# 04C-004_Adjustable_Analog_Front_End.net
KiCad netlist of a schematic drawn in EAGLE
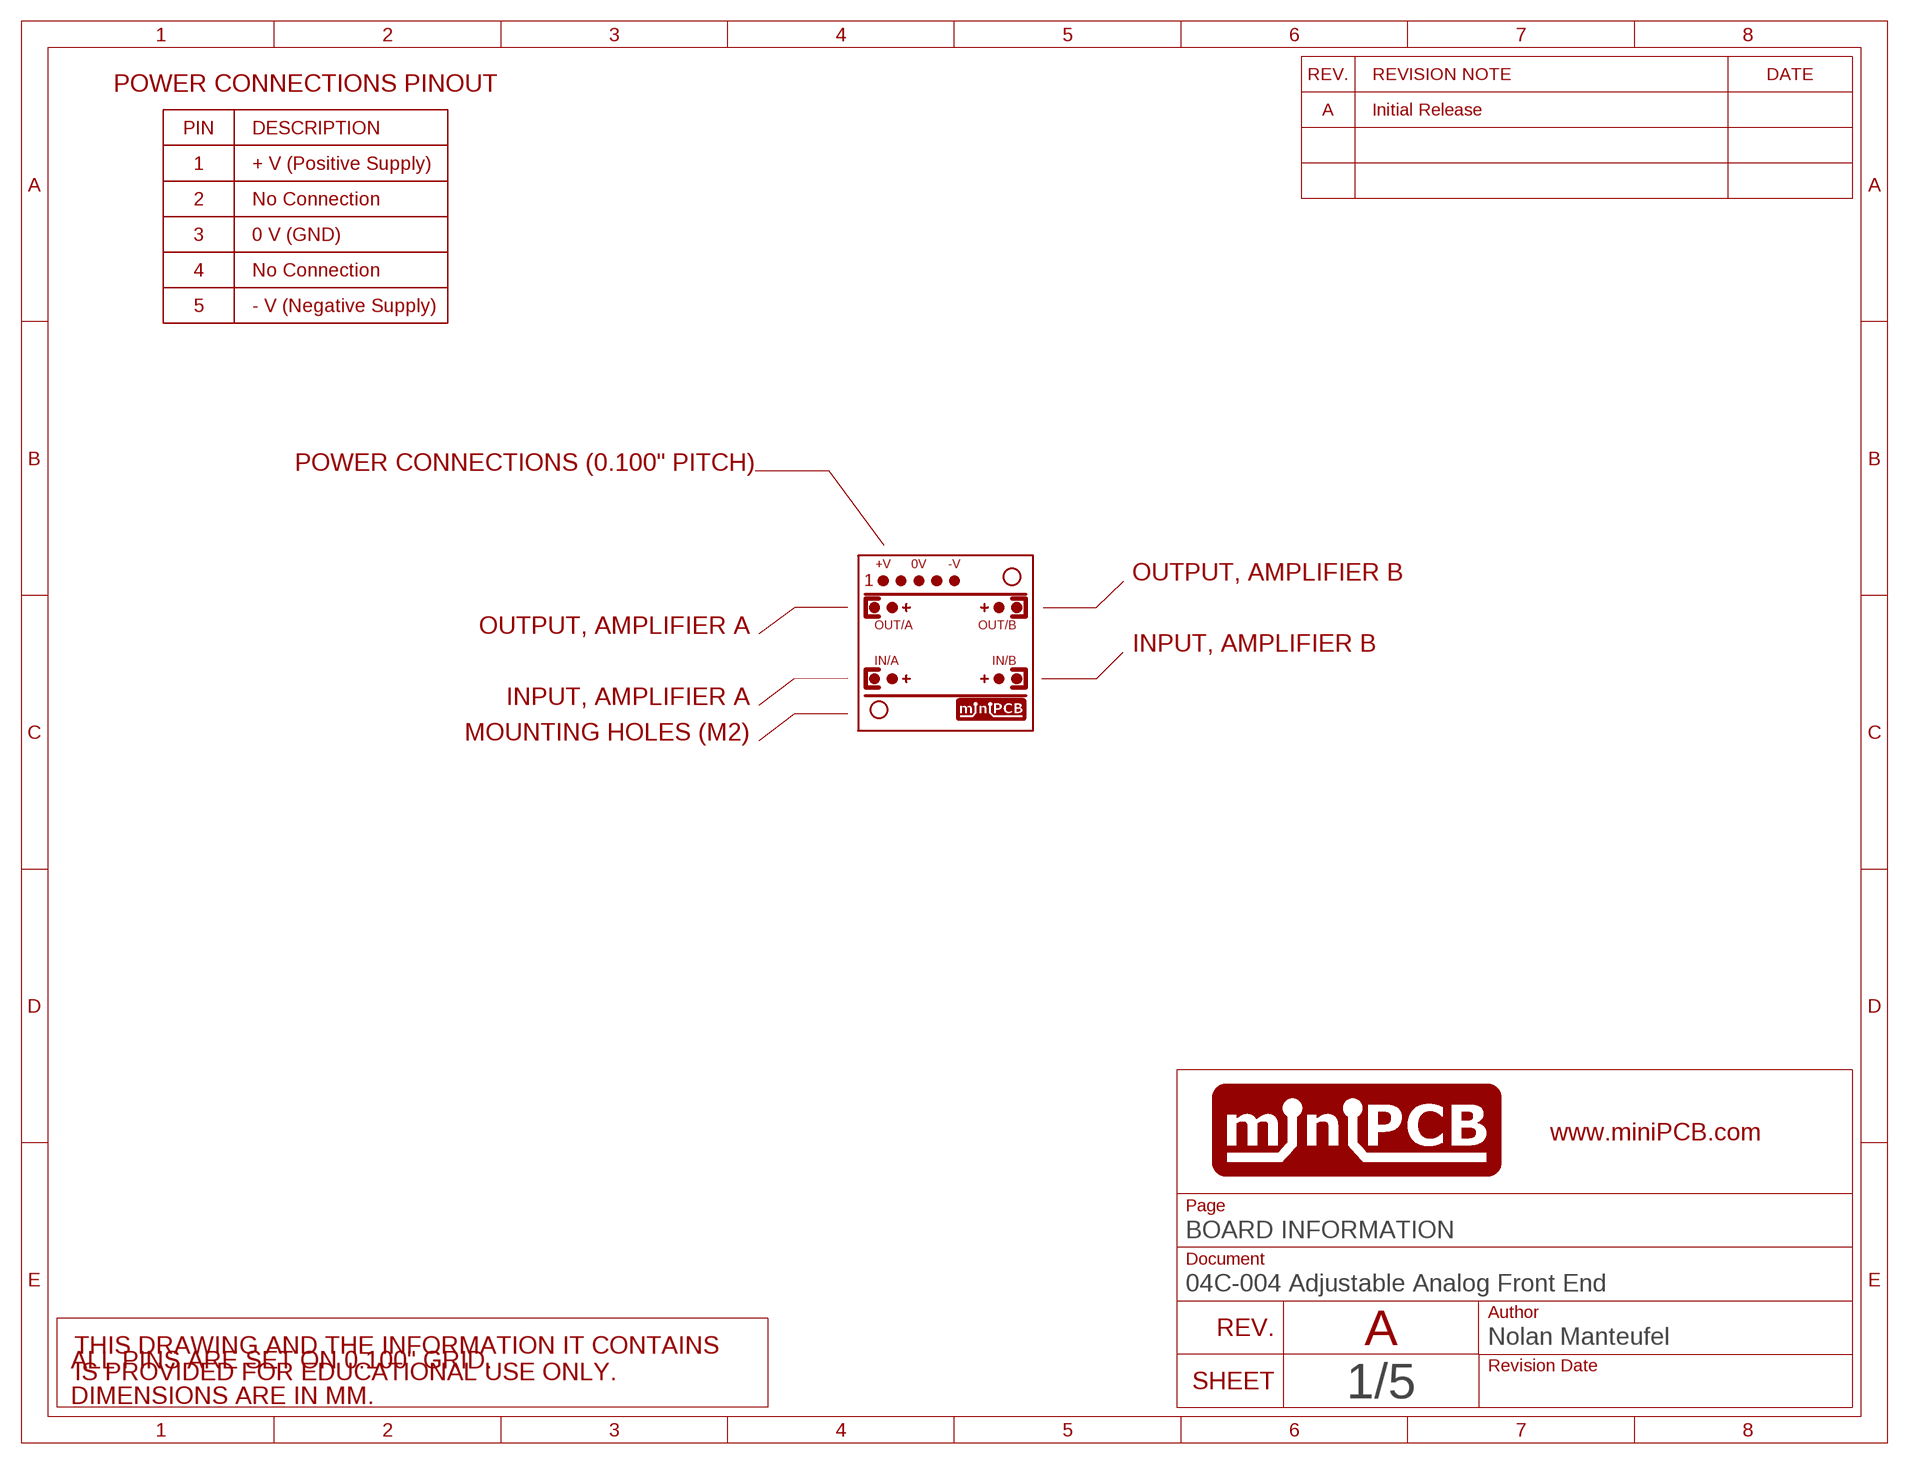
[diagram p0: schematic, sheet 1]
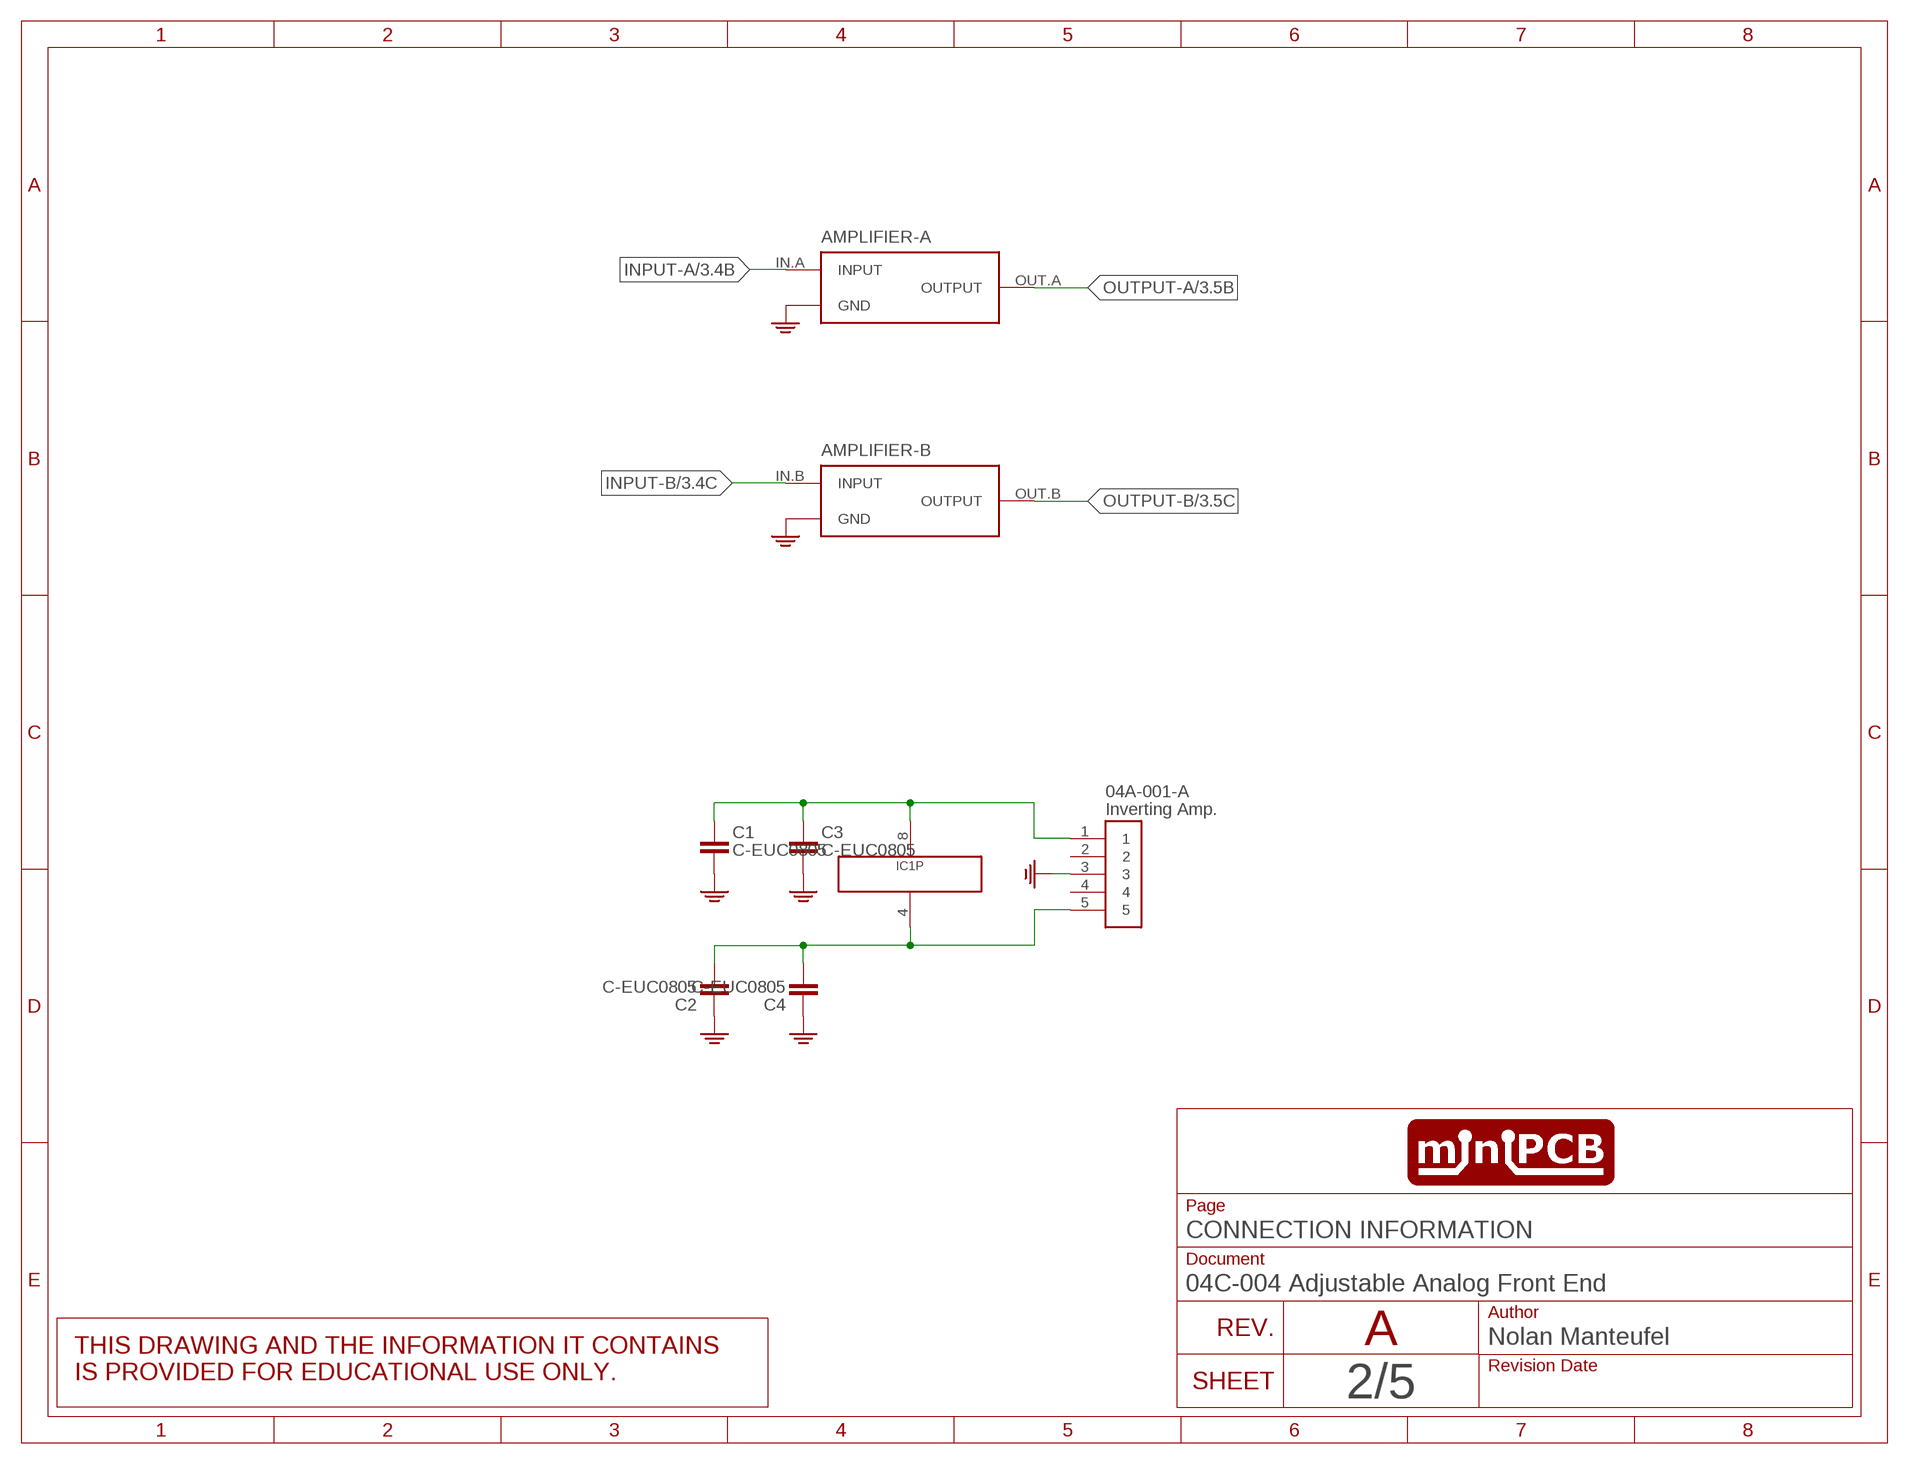
[diagram p1: schematic, sheet 2]
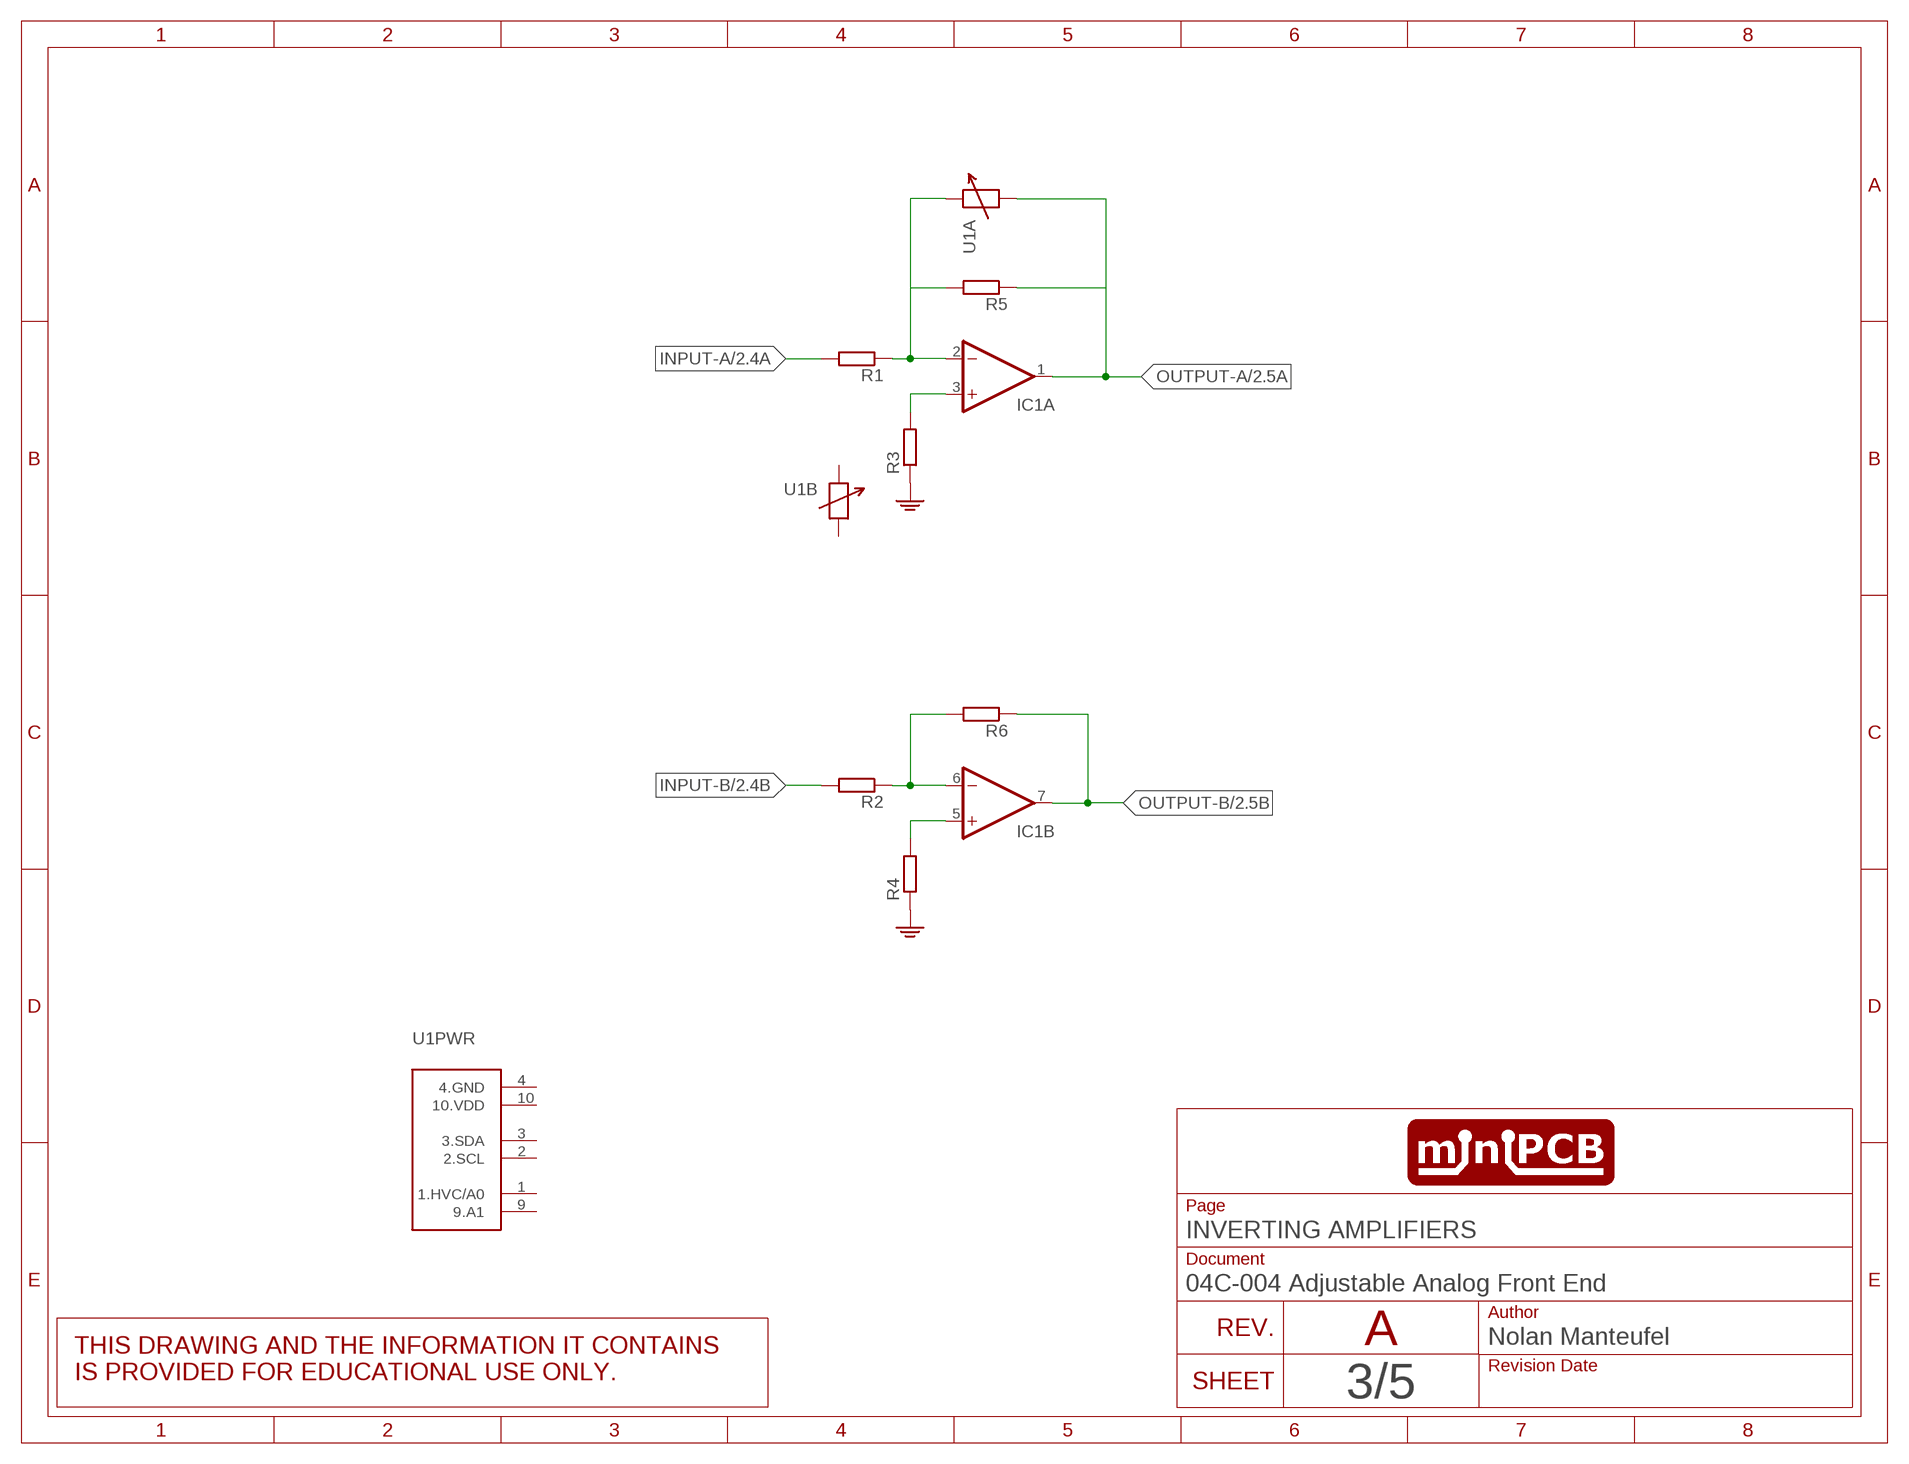
[diagram p2: schematic, sheet 3]
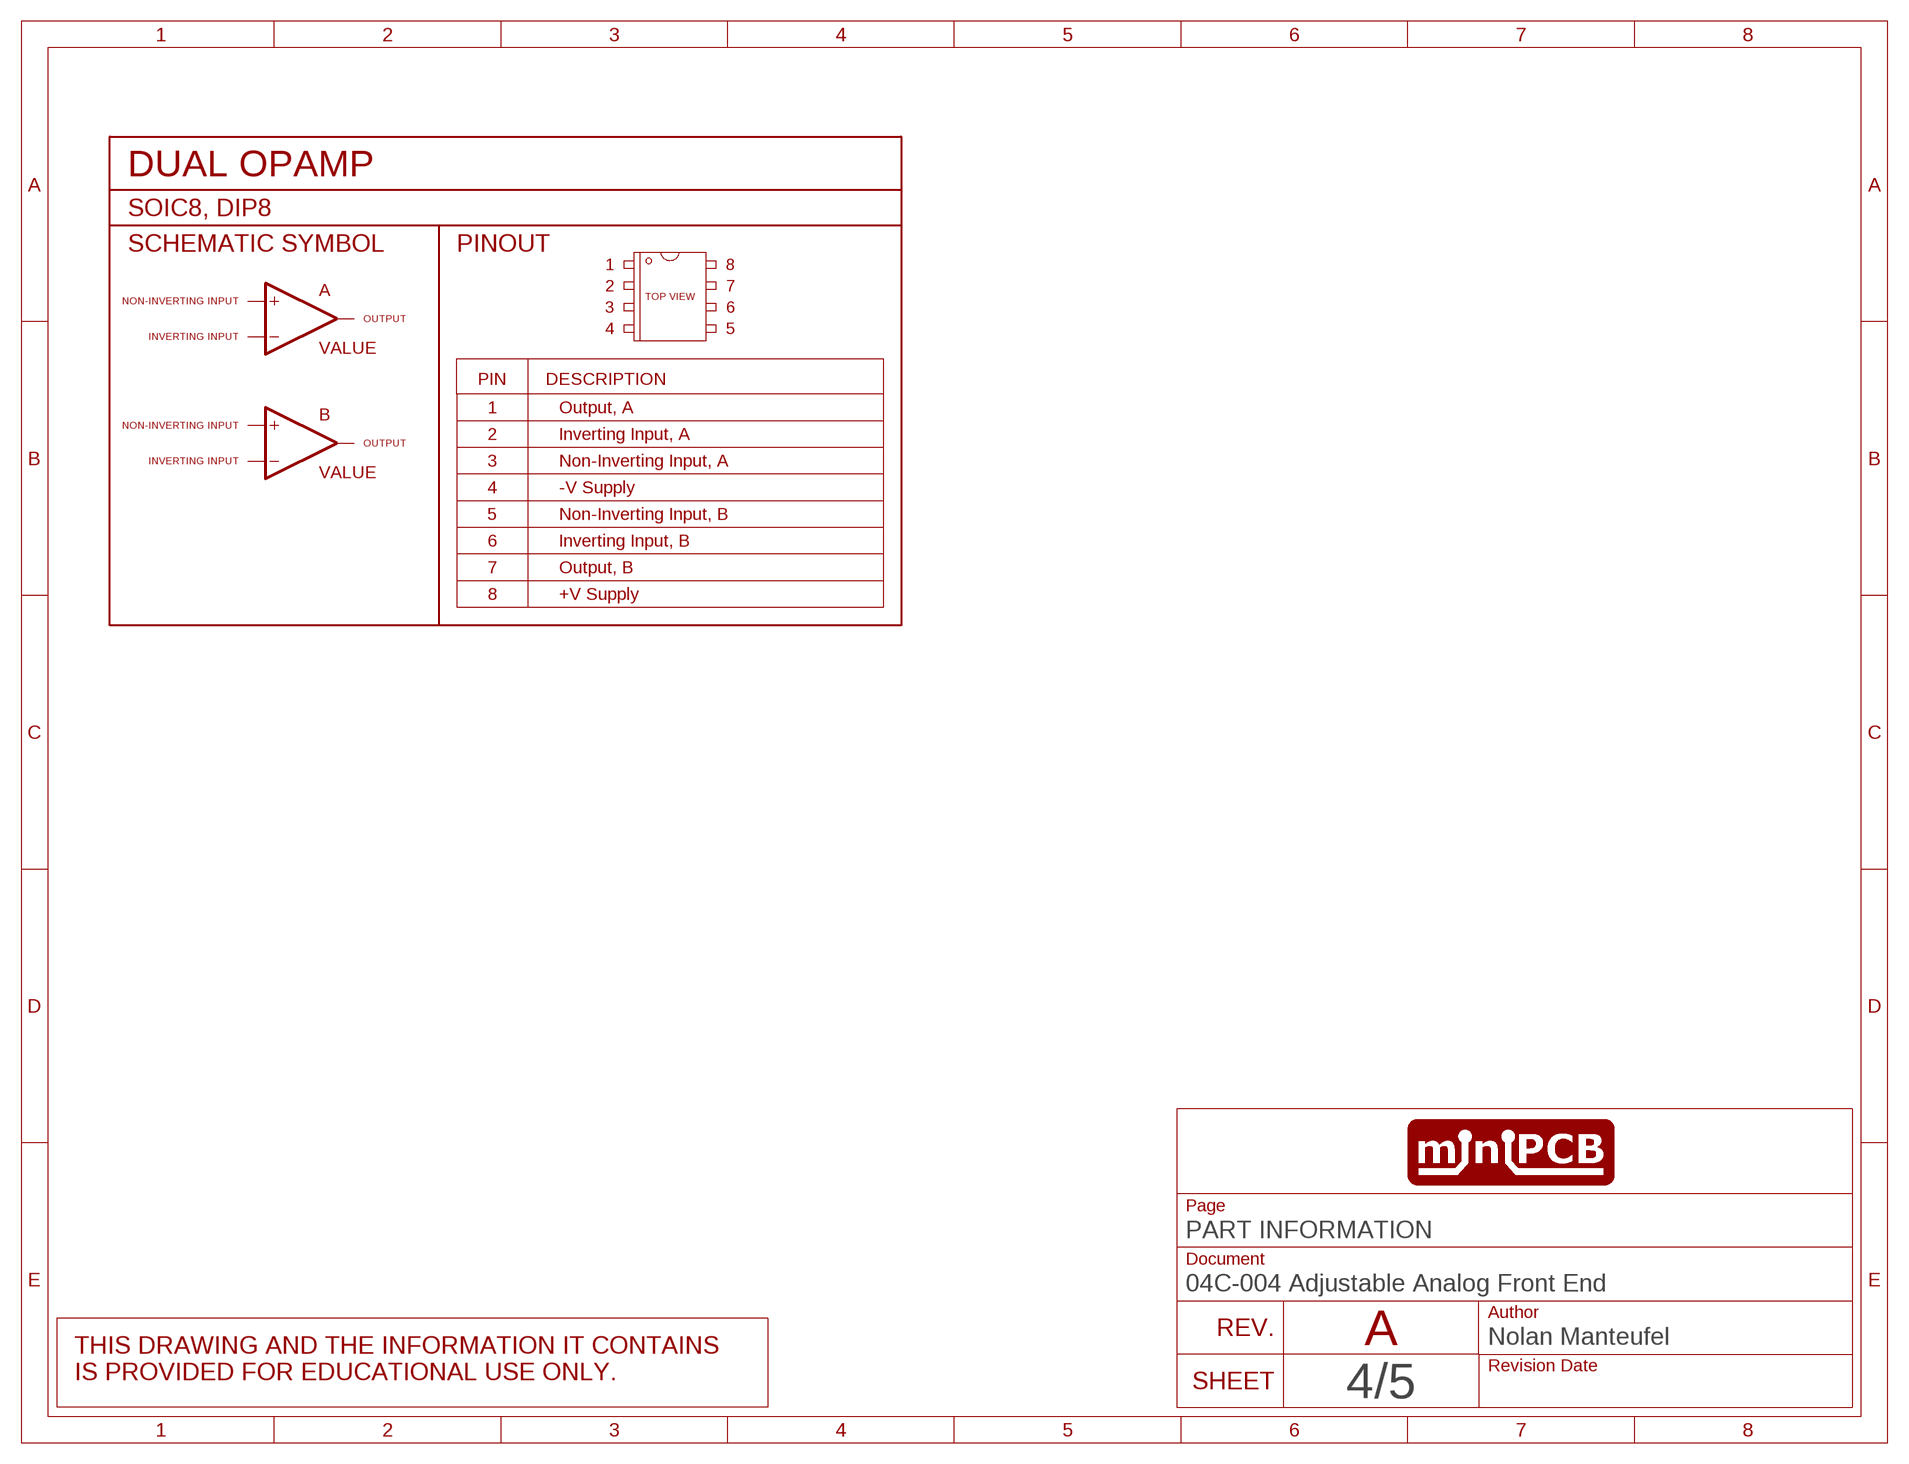
[diagram p3: schematic, sheet 4]
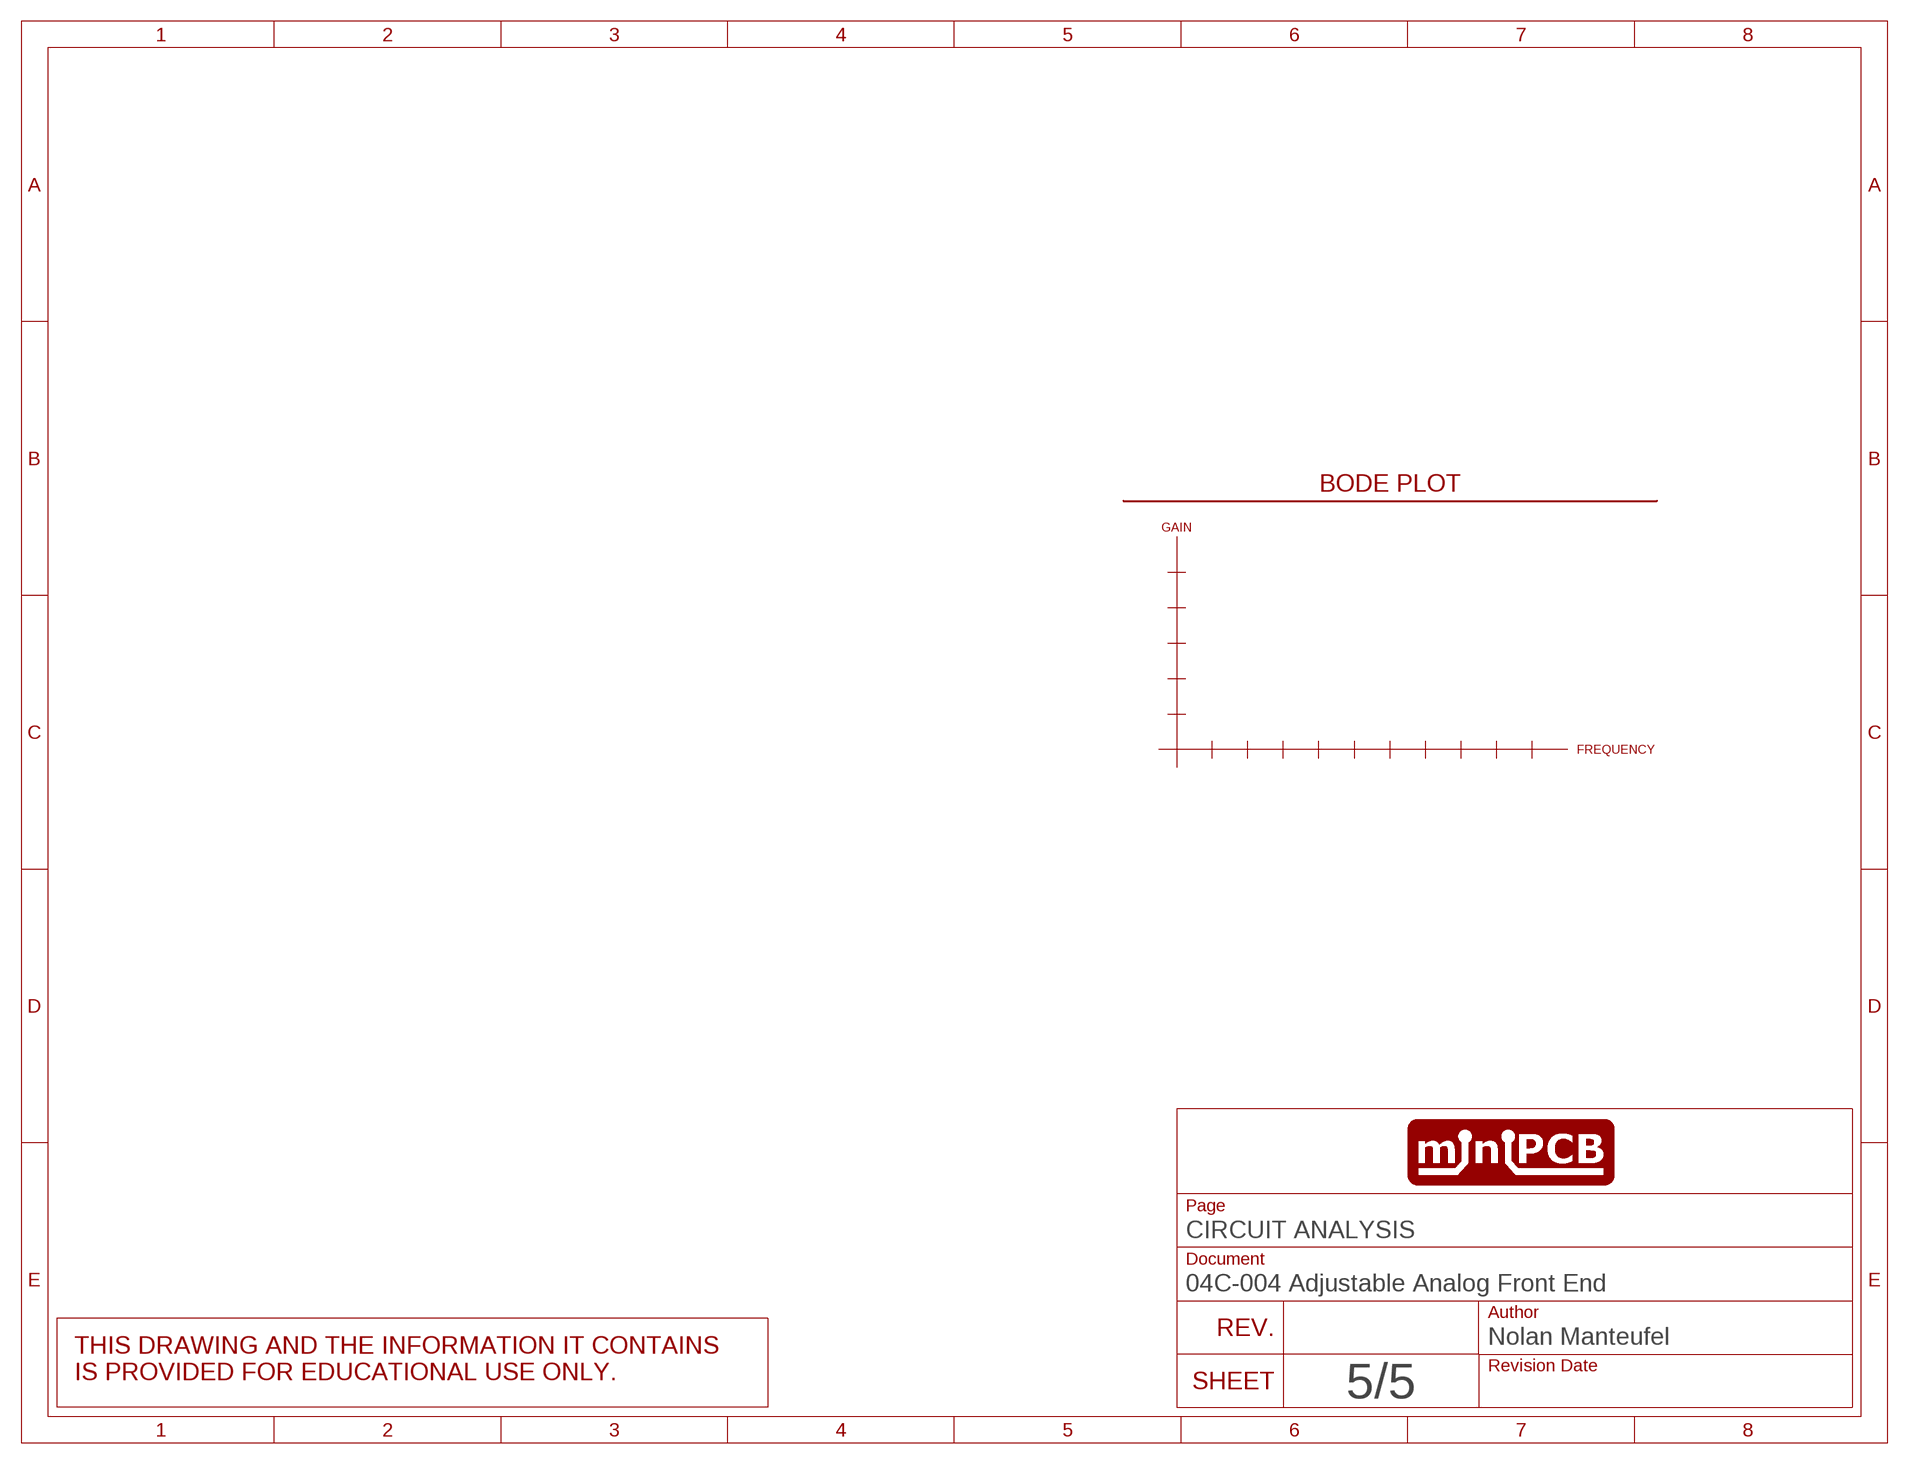
[diagram p4: schematic, sheet 5]

(export (version "E")
  (design (tool "Eeschema 10.0.6"))
  (components
    (comp (ref "IC1")
      (value "LF412D")
      (footprint "eagle-import:SO08")
      (libsource (lib "eagle-import") (part "LF412D"))
    )
    (comp (ref "R1")
      (value "R-EU_R0805")
      (footprint "eagle-import:R0805")
      (libsource (lib "eagle-import") (part "R-EU_R0805"))
    )
    (comp (ref "R2")
      (value "R-EU_R0805")
      (footprint "eagle-import:R0805")
      (libsource (lib "eagle-import") (part "R-EU_R0805"))
    )
    (comp (ref "R3")
      (value "R-EU_R0805")
      (footprint "eagle-import:R0805")
      (libsource (lib "eagle-import") (part "R-EU_R0805"))
    )
    (comp (ref "R4")
      (value "R-EU_R0805")
      (footprint "eagle-import:R0805")
      (libsource (lib "eagle-import") (part "R-EU_R0805"))
    )
    (comp (ref "R5")
      (value "R-EU_R0805")
      (footprint "eagle-import:R0805")
      (libsource (lib "eagle-import") (part "R-EU_R0805"))
    )
    (comp (ref "R6")
      (value "R-EU_R0805")
      (footprint "eagle-import:R0805")
      (libsource (lib "eagle-import") (part "R-EU_R0805"))
    )
    (comp (ref "U1")
      (value "MCP4542T")
      (footprint "eagle-import:MMSOP10")
      (libsource (lib "eagle-import") (part "MCP4542T"))
    )
    (comp (ref "04A-001-A")
      (value "Inverting Amp.")
      (footprint "eagle-import:MINIPCB_25X25MM")
      (libsource (lib "eagle-import") (part "MINIPCB_5P25MM"))
    )
    (comp (ref "AMPLIFIER-")
      (value "MINIPCB_AMP-DUAL25-T")
      (footprint "eagle-import:MINIPCB_25MM-AMP-DUAL-VTEXT")
      (libsource (lib "eagle-import") (part "MINIPCB_AMP-DUAL25-T"))
    )
    (comp (ref "C1")
      (value "C-EUC0805")
      (footprint "eagle-import:C0805")
      (libsource (lib "eagle-import") (part "C-EUC0805"))
    )
    (comp (ref "C2")
      (value "C-EUC0805")
      (footprint "eagle-import:C0805")
      (libsource (lib "eagle-import") (part "C-EUC0805"))
    )
    (comp (ref "C3")
      (value "C-EUC0805")
      (footprint "eagle-import:C0805")
      (libsource (lib "eagle-import") (part "C-EUC0805"))
    )
    (comp (ref "C4")
      (value "C-EUC0805")
      (footprint "eagle-import:C0805")
      (libsource (lib "eagle-import") (part "C-EUC0805"))
    )
  )
  (nets
    (net (code "1") (name "GND") (class "Default")
      (node (ref "04A-001-A") (pin "3") (pinfunction "3_3") (pintype "bidirectional"))
      (node (ref "AMPLIFIER-") (pin "GND.A1") (pinfunction "GND_GND.A1") (pintype "bidirectional"))
      (node (ref "AMPLIFIER-") (pin "GND.A2") (pinfunction "GND_GND.A2") (pintype "bidirectional"))
      (node (ref "AMPLIFIER-") (pin "GND.B1") (pinfunction "GND_GND.B1") (pintype "bidirectional"))
      (node (ref "AMPLIFIER-") (pin "GND.B2") (pinfunction "GND_GND.B2") (pintype "bidirectional"))
      (node (ref "C1") (pin "2") (pinfunction "2_2") (pintype "passive"))
      (node (ref "C2") (pin "1") (pinfunction "1_1") (pintype "passive"))
      (node (ref "C3") (pin "2") (pinfunction "2_2") (pintype "passive"))
      (node (ref "C4") (pin "1") (pinfunction "1_1") (pintype "passive"))
      (node (ref "R3") (pin "1") (pinfunction "1_1") (pintype "passive"))
      (node (ref "R4") (pin "1") (pinfunction "1_1") (pintype "passive"))
    )
    (net (code "2") (name "INPUT-A") (class "Default")
      (node (ref "AMPLIFIER-") (pin "IN.A") (pinfunction "INPUT_IN.A") (pintype "bidirectional"))
      (node (ref "R1") (pin "2") (pinfunction "2_2") (pintype "passive"))
    )
    (net (code "3") (name "INPUT-B") (class "Default")
      (node (ref "AMPLIFIER-") (pin "IN.B") (pinfunction "INPUT_IN.B") (pintype "bidirectional"))
      (node (ref "R2") (pin "2") (pinfunction "2_2") (pintype "passive"))
    )
    (net (code "4") (name "Net-(IC1A-+IN)") (class "Default")
      (node (ref "IC1") (pin "3") (pinfunction "+IN_3") (pintype "input"))
      (node (ref "R3") (pin "2") (pinfunction "2_2") (pintype "passive"))
    )
    (net (code "5") (name "Net-(IC1A--IN)") (class "Default")
      (node (ref "IC1") (pin "2") (pinfunction "-IN_2") (pintype "input"))
      (node (ref "R1") (pin "1") (pinfunction "1_1") (pintype "passive"))
      (node (ref "R5") (pin "2") (pinfunction "2_2") (pintype "passive"))
      (node (ref "U1") (pin "8") (pinfunction "B_8") (pintype "bidirectional"))
    )
    (net (code "6") (name "Net-(IC1B-+IN)") (class "Default")
      (node (ref "IC1") (pin "5") (pinfunction "+IN_5") (pintype "input"))
      (node (ref "R4") (pin "2") (pinfunction "2_2") (pintype "passive"))
    )
    (net (code "7") (name "Net-(IC1B--IN)") (class "Default")
      (node (ref "IC1") (pin "6") (pinfunction "-IN_6") (pintype "input"))
      (node (ref "R2") (pin "1") (pinfunction "1_1") (pintype "passive"))
      (node (ref "R6") (pin "2") (pinfunction "2_2") (pintype "passive"))
    )
    (net (code "8") (name "Net-(IC1C-V+)") (class "Default")
      (node (ref "04A-001-A") (pin "1") (pinfunction "1_1") (pintype "bidirectional"))
      (node (ref "C1") (pin "1") (pinfunction "1_1") (pintype "passive"))
      (node (ref "C3") (pin "1") (pinfunction "1_1") (pintype "passive"))
      (node (ref "IC1") (pin "8") (pinfunction "V+_8") (pintype "power_in"))
    )
    (net (code "9") (name "Net-(IC1C-V-)") (class "Default")
      (node (ref "04A-001-A") (pin "5") (pinfunction "5_5") (pintype "bidirectional"))
      (node (ref "C2") (pin "2") (pinfunction "2_2") (pintype "passive"))
      (node (ref "C4") (pin "2") (pinfunction "2_2") (pintype "passive"))
      (node (ref "IC1") (pin "4") (pinfunction "V-_4") (pintype "power_in"))
    )
    (net (code "10") (name "OUTPUT-A") (class "Default")
      (node (ref "AMPLIFIER-") (pin "OUT.A") (pinfunction "OUTPUT_OUT.A") (pintype "bidirectional"))
      (node (ref "IC1") (pin "1") (pinfunction "OUT_1") (pintype "output"))
      (node (ref "R5") (pin "1") (pinfunction "1_1") (pintype "passive"))
      (node (ref "U1") (pin "7") (pinfunction "W_7") (pintype "bidirectional"))
    )
    (net (code "11") (name "OUTPUT-B") (class "Default")
      (node (ref "AMPLIFIER-") (pin "OUT.B") (pinfunction "OUTPUT_OUT.B") (pintype "bidirectional"))
      (node (ref "IC1") (pin "7") (pinfunction "OUT_7") (pintype "output"))
      (node (ref "R6") (pin "1") (pinfunction "1_1") (pintype "passive"))
    )
    (net (code "12") (name "unconnected-(04A-001-A-Pad2)") (class "Default")
      (node (ref "04A-001-A") (pin "2") (pinfunction "2_2") (pintype "bidirectional"))
    )
    (net (code "13") (name "unconnected-(04A-001-A-Pad4)") (class "Default")
      (node (ref "04A-001-A") (pin "4") (pinfunction "4_4") (pintype "bidirectional"))
    )
    (net (code "14") (name "unconnected-(U1B-B-Pad5)") (class "Default")
      (node (ref "U1") (pin "5") (pinfunction "B_5") (pintype "bidirectional"))
    )
    (net (code "15") (name "unconnected-(U1B-W-Pad6)") (class "Default")
      (node (ref "U1") (pin "6") (pinfunction "W_6") (pintype "bidirectional"))
    )
    (net (code "16") (name "unconnected-(U1C-1.HVC{slash}A0-Pad1)") (class "Default")
      (node (ref "U1") (pin "1") (pinfunction "1.HVC/A0_1") (pintype "bidirectional"))
    )
    (net (code "17") (name "unconnected-(U1C-2.SCL-Pad2)") (class "Default")
      (node (ref "U1") (pin "2") (pinfunction "2.SCL_2") (pintype "bidirectional"))
    )
    (net (code "18") (name "unconnected-(U1C-3.SDA-Pad3)") (class "Default")
      (node (ref "U1") (pin "3") (pinfunction "3.SDA_3") (pintype "bidirectional"))
    )
    (net (code "19") (name "unconnected-(U1C-4.GND-Pad4)") (class "Default")
      (node (ref "U1") (pin "4") (pinfunction "4.GND_4") (pintype "bidirectional"))
    )
    (net (code "20") (name "unconnected-(U1C-9.A1-Pad9)") (class "Default")
      (node (ref "U1") (pin "9") (pinfunction "9.A1_9") (pintype "bidirectional"))
    )
    (net (code "21") (name "unconnected-(U1C-10.VDD-Pad10)") (class "Default")
      (node (ref "U1") (pin "10") (pinfunction "10.VDD_10") (pintype "bidirectional"))
    )
  )
)
